# 8_-_DAC_and_MIC.net
KiCad netlist of a schematic drawn in Altium Designer
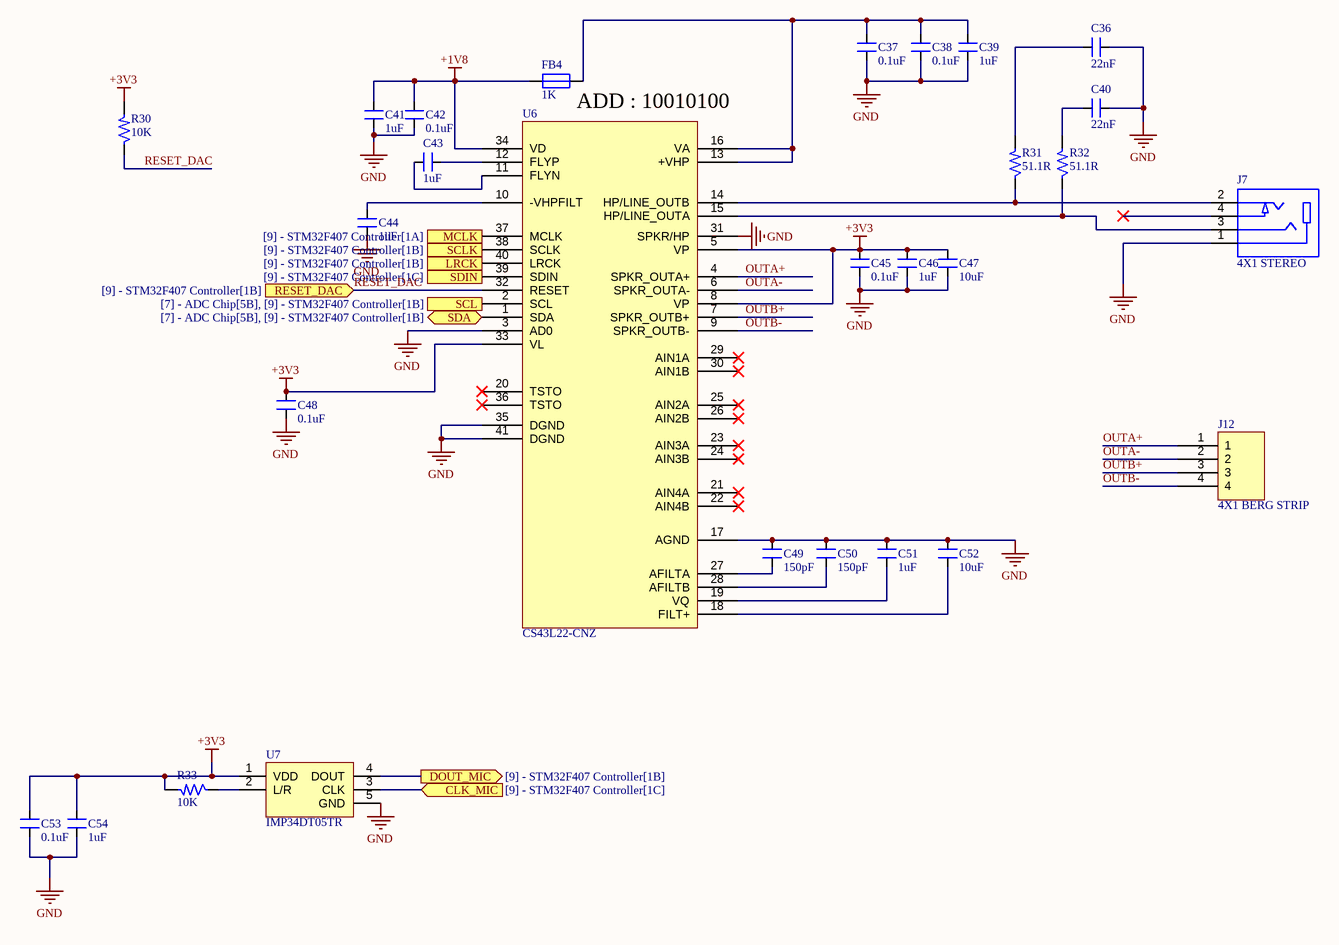
[diagram p0: [8] - DAC and MIC.SchDoc]

(export (version "E")
  (design (tool "Eeschema 10.0.6"))
  (components
    (comp (ref "C36")
      (value "22nF")
      (footprint "CAP_0805")
      (description "0.022µF ±10% 50V Ceramic Capacitor X7R 0805 (2012 Metric)")
      (fields
        (field (name "MANUFACTURER") "Samsung Electro-Mechanics")
        (field (name "MANUFACTURER PART NUMBER") "CL21B223KBANNNC")
      )
      (libsource (lib "ESTEEMPCBLIB") (part "CAP_22nF-50V-10%-0805"))
    )
    (comp (ref "C37")
      (value "0.1uF")
      (footprint "CAP_0805")
      (description "0.1µF ±10% 50V Ceramic Capacitor X7R 0805 (2012 Metric)")
      (fields
        (field (name "MANUFACTURER") "Samsung")
        (field (name "MANUFACTURER PART NUMBER") "CL21B104KBCNNNC")
      )
      (libsource (lib "ESTEEMPCBLIB") (part "CAP_0.1uF-50V-10%-0805"))
    )
    (comp (ref "C38")
      (value "0.1uF")
      (footprint "CAP_0805")
      (description "0.1µF ±10% 50V Ceramic Capacitor X7R 0805 (2012 Metric)")
      (fields
        (field (name "MANUFACTURER") "Samsung")
        (field (name "MANUFACTURER PART NUMBER") "CL21B104KBCNNNC")
      )
      (libsource (lib "ESTEEMPCBLIB") (part "CAP_0.1uF-50V-10%-0805"))
    )
    (comp (ref "C39")
      (value "1uF")
      (footprint "CAP_0805")
      (description "1µF ±5% 50V Ceramic Capacitor X7R 0805 (2012 Metric)")
      (fields
        (field (name "MANUFACTURER") "Samsung")
        (field (name "MANUFACTURER PART NUMBER") "CC0805JKX7R9BB105")
      )
      (libsource (lib "ESTEEMPCBLIB") (part "CAP_1uF-50V-5%-0805"))
    )
    (comp (ref "C40")
      (value "22nF")
      (footprint "CAP_0805")
      (description "0.022µF ±10% 50V Ceramic Capacitor X7R 0805 (2012 Metric)")
      (fields
        (field (name "MANUFACTURER") "Samsung Electro-Mechanics")
        (field (name "MANUFACTURER PART NUMBER") "CL21B223KBANNNC")
      )
      (libsource (lib "ESTEEMPCBLIB") (part "CAP_22nF-50V-10%-0805"))
    )
    (comp (ref "C41")
      (value "1uF")
      (footprint "CAP_0805")
      (description "1µF ±5% 50V Ceramic Capacitor X7R 0805 (2012 Metric)")
      (fields
        (field (name "MANUFACTURER") "Samsung")
        (field (name "MANUFACTURER PART NUMBER") "CC0805JKX7R9BB105")
      )
      (libsource (lib "ESTEEMPCBLIB") (part "CAP_1uF-50V-5%-0805"))
    )
    (comp (ref "C42")
      (value "0.1uF")
      (footprint "CAP_0805")
      (description "0.1µF ±10% 50V Ceramic Capacitor X7R 0805 (2012 Metric)")
      (fields
        (field (name "MANUFACTURER") "Samsung")
        (field (name "MANUFACTURER PART NUMBER") "CL21B104KBCNNNC")
      )
      (libsource (lib "ESTEEMPCBLIB") (part "CAP_0.1uF-50V-10%-0805"))
    )
    (comp (ref "C43")
      (value "1uF")
      (footprint "CAP_0805")
      (description "1µF ±5% 50V Ceramic Capacitor X7R 0805 (2012 Metric)")
      (fields
        (field (name "MANUFACTURER") "Samsung")
        (field (name "MANUFACTURER PART NUMBER") "CC0805JKX7R9BB105")
      )
      (libsource (lib "ESTEEMPCBLIB") (part "CAP_1uF-50V-5%-0805"))
    )
    (comp (ref "C44")
      (value "1uF")
      (footprint "CAP_0805")
      (description "1µF ±5% 50V Ceramic Capacitor X7R 0805 (2012 Metric)")
      (fields
        (field (name "MANUFACTURER") "Samsung")
        (field (name "MANUFACTURER PART NUMBER") "CC0805JKX7R9BB105")
      )
      (libsource (lib "ESTEEMPCBLIB") (part "CAP_1uF-50V-5%-0805"))
    )
    (comp (ref "C45")
      (value "0.1uF")
      (footprint "CAP_0805")
      (description "0.1µF ±10% 50V Ceramic Capacitor X7R 0805 (2012 Metric)")
      (fields
        (field (name "MANUFACTURER") "Samsung")
        (field (name "MANUFACTURER PART NUMBER") "CL21B104KBCNNNC")
      )
      (libsource (lib "ESTEEMPCBLIB") (part "CAP_0.1uF-50V-10%-0805"))
    )
    (comp (ref "C46")
      (value "1uF")
      (footprint "CAP_0805")
      (description "1µF ±5% 50V Ceramic Capacitor X7R 0805 (2012 Metric)")
      (fields
        (field (name "MANUFACTURER") "Samsung")
        (field (name "MANUFACTURER PART NUMBER") "CC0805JKX7R9BB105")
      )
      (libsource (lib "ESTEEMPCBLIB") (part "CAP_1uF-50V-5%-0805"))
    )
    (comp (ref "C47")
      (value "10uF")
      (footprint "CAP_1206")
      (description "10µF ±10% 50V Ceramic Capacitor X7R 1206 (3216 Metric)")
      (fields
        (field (name "MANUFACTURER") "KEMET")
        (field (name "MANUFACTURER PART NUMBER") "CL31B106KBHNNNE")
      )
      (libsource (lib "ESTEEMPCBLIB") (part "CAP_10uF-50V-10%-1206"))
    )
    (comp (ref "C48")
      (value "0.1uF")
      (footprint "CAP_0805")
      (description "0.1µF ±10% 50V Ceramic Capacitor X7R 0805 (2012 Metric)")
      (fields
        (field (name "MANUFACTURER") "Samsung")
        (field (name "MANUFACTURER PART NUMBER") "CL21B104KBCNNNC")
      )
      (libsource (lib "ESTEEMPCBLIB") (part "CAP_0.1uF-50V-10%-0805"))
    )
    (comp (ref "C49")
      (value "150pF")
      (footprint "CAP_0805")
      (description "150pF ±10% 50V Ceramic Capacitor C0G, NP0 0805 (2012 Metric)")
      (fields
        (field (name "MANUFACTURER") "AVX Corporation")
        (field (name "MANUFACTURER PART NUMBER") "08055A151KAT2A")
      )
      (libsource (lib "ESTEEMPCBLIB") (part "CAP_150pF-50V-10%-0805"))
    )
    (comp (ref "C50")
      (value "150pF")
      (footprint "CAP_0805")
      (description "150pF ±10% 50V Ceramic Capacitor C0G, NP0 0805 (2012 Metric)")
      (fields
        (field (name "MANUFACTURER") "AVX Corporation")
        (field (name "MANUFACTURER PART NUMBER") "08055A151KAT2A")
      )
      (libsource (lib "ESTEEMPCBLIB") (part "CAP_150pF-50V-10%-0805"))
    )
    (comp (ref "C51")
      (value "1uF")
      (footprint "CAP_0805")
      (description "1µF ±5% 50V Ceramic Capacitor X7R 0805 (2012 Metric)")
      (fields
        (field (name "MANUFACTURER") "Samsung")
        (field (name "MANUFACTURER PART NUMBER") "CC0805JKX7R9BB105")
      )
      (libsource (lib "ESTEEMPCBLIB") (part "CAP_1uF-50V-5%-0805"))
    )
    (comp (ref "C52")
      (value "10uF")
      (footprint "CAP_1206")
      (description "10µF ±10% 50V Ceramic Capacitor X7R 1206 (3216 Metric)")
      (fields
        (field (name "MANUFACTURER") "KEMET")
        (field (name "MANUFACTURER PART NUMBER") "CL31B106KBHNNNE")
      )
      (libsource (lib "ESTEEMPCBLIB") (part "CAP_10uF-50V-10%-1206"))
    )
    (comp (ref "C53")
      (value "0.1uF")
      (footprint "CAP_0805")
      (description "0.1µF ±10% 50V Ceramic Capacitor X7R 0805 (2012 Metric)")
      (fields
        (field (name "MANUFACTURER") "Samsung")
        (field (name "MANUFACTURER PART NUMBER") "CL21B104KBCNNNC")
      )
      (libsource (lib "ESTEEMPCBLIB") (part "CAP_0.1uF-50V-10%-0805"))
    )
    (comp (ref "C54")
      (value "1uF")
      (footprint "CAP_0805")
      (description "1µF ±5% 50V Ceramic Capacitor X7R 0805 (2012 Metric)")
      (fields
        (field (name "MANUFACTURER") "Samsung")
        (field (name "MANUFACTURER PART NUMBER") "CC0805JKX7R9BB105")
      )
      (libsource (lib "ESTEEMPCBLIB") (part "CAP_1uF-50V-5%-0805"))
    )
    (comp (ref "FB4")
      (value "1K")
      (footprint "IND_0805")
      (description "1 kOhms @ 100MHz 1 Power Line Ferrite Bead 0805 (2012 Metric) 1.6A")
      (fields
        (field (name "MANUFACTURER") "Laird")
        (field (name "MANUFACTURER PART NUMBER") "BLM21SP102SH1D")
      )
      (libsource (lib "ESTEEMPCBLIB") (part "FB_1K-100MHZ-1.6A-0805"))
    )
    (comp (ref "J7")
      (value "4X1 STEREO")
      (footprint "CON_SJ-2504A-SMT-TR_SMD")
      (fields
        (field (name "MANUFACTURER") "CUI Devices")
        (field (name "MANUFACTURER PART NUMBER") "SJ-2504A-SMT-TR")
      )
      (libsource (lib "ESTEEMPCBLIB") (part "CON-PLG-STEREO_4X1-100-RA-SMD"))
    )
    (comp (ref "J12")
      (value "4X1 BERG STRIP")
      (footprint "CON4_100_40D72_TH_ST_MALE")
      (description "4 Pins, 1 Row 2.54mm Pitch, Straight bergstrip, Male")
      (fields (field (name "MANUFACTURER") "NA"))
      (libsource (lib "ESTEEMPCBLIB") (part "CON-BS-PLG_4X1-100-ST-TH"))
    )
    (comp (ref "R30")
      (value "10K")
      (footprint "RES_0603")
      (description "10 kOhms ±1% 0.1W, 1/10W Chip Resistor 0603 (1608 Metric) Automotive AEC-Q200 Thick Film")
      (fields (field (name "MANUFACTURER") "Walsin") (field (name "MANUFACTURER PART NUMBER") "WR06X1002FTL"))
      (libsource (lib "ESTEEMPCBLIB") (part "RES_10K-0.1W-1%-0603"))
    )
    (comp (ref "R31")
      (value "51.1R")
      (footprint "RES_0603")
      (description "51.1 Ohms ±1% 0.1W, 1/10W Chip Resistor 0603 (1608 Metric) Thick Film")
      (fields
        (field (name "MANUFACTURER") "Vishay Dale")
        (field (name "MANUFACTURER PART NUMBER") "CRCW060351R1FKEAC")
      )
      (libsource (lib "ESTEEMPCBLIB") (part "RES_51.1R-0.1W-1%-0603"))
    )
    (comp (ref "R32")
      (value "51.1R")
      (footprint "RES_0603")
      (description "51.1 Ohms ±1% 0.1W, 1/10W Chip Resistor 0603 (1608 Metric) Thick Film")
      (fields
        (field (name "MANUFACTURER") "Vishay Dale")
        (field (name "MANUFACTURER PART NUMBER") "CRCW060351R1FKEAC")
      )
      (libsource (lib "ESTEEMPCBLIB") (part "RES_51.1R-0.1W-1%-0603"))
    )
    (comp (ref "R33")
      (value "10K")
      (footprint "RES_0603")
      (description "10 kOhms ±1% 0.1W, 1/10W Chip Resistor 0603 (1608 Metric) Automotive AEC-Q200 Thick Film")
      (fields (field (name "MANUFACTURER") "Walsin") (field (name "MANUFACTURER PART NUMBER") "WR06X1002FTL"))
      (libsource (lib "ESTEEMPCBLIB") (part "RES_10K-0.1W-1%-0603"))
    )
    (comp (ref "U6")
      (value "CS43L22-CNZ")
      (footprint "QFN40_19_284_33X9_SMD")
      (description "Audio D/A Converter ICs Low Power Stereo DAC w/ClassD Spkr Driver")
      (fields (field (name "MANUFACTURER") "Cirrus Logic"))
      (libsource (lib "ESTEEMPCBLIB") (part "IC_CS43L22"))
    )
    (comp (ref "U7")
      (value "IMP34DT05TR")
      (footprint "HCLGA-4_53_137_15X37_SMD")
      (description "MEMS Microphones AUTO & INDUSTRIAL SENSORS")
      (fields (field (name "MANUFACTURER") "STMicroelectronics"))
      (libsource (lib "ESTEEMPCBLIB") (part "IC_IMP34DT05TR"))
    )
  )
  (nets
    (net (code "1") (name "+1V8") (class "Default")
      (node (ref "C41") (pin "2") (pinfunction "2_2") (pintype "passive"))
      (node (ref "C42") (pin "2") (pinfunction "2_2") (pintype "passive"))
      (node (ref "FB4") (pin "1") (pinfunction "1_1") (pintype "passive"))
      (node (ref "U6") (pin "34") (pinfunction "VD_34") (pintype "passive"))
    )
    (net (code "2") (name "+3V3") (class "Default")
      (node (ref "C45") (pin "2") (pinfunction "2_2") (pintype "passive"))
      (node (ref "C46") (pin "2") (pinfunction "2_2") (pintype "passive"))
      (node (ref "C47") (pin "1") (pinfunction "1_1") (pintype "passive"))
      (node (ref "C48") (pin "2") (pinfunction "2_2") (pintype "passive"))
      (node (ref "C53") (pin "2") (pinfunction "2_2") (pintype "passive"))
      (node (ref "C54") (pin "2") (pinfunction "2_2") (pintype "passive"))
      (node (ref "R30") (pin "2") (pinfunction "2_2") (pintype "passive"))
      (node (ref "R33") (pin "2") (pinfunction "2_2") (pintype "passive"))
      (node (ref "U6") (pin "33") (pinfunction "VL_33") (pintype "passive"))
      (node (ref "U6") (pin "5") (pinfunction "VP_5") (pintype "passive"))
      (node (ref "U6") (pin "8") (pinfunction "VP_8") (pintype "passive"))
      (node (ref "U7") (pin "1") (pinfunction "VDD_1") (pintype "passive"))
    )
    (net (code "3") (name "/CLK_MIC") (class "Default")
      (node (ref "U7") (pin "3") (pinfunction "CLK_3") (pintype "passive"))
    )
    (net (code "4") (name "/DOUT_MIC") (class "Default")
      (node (ref "U7") (pin "4") (pinfunction "DOUT_4") (pintype "passive"))
    )
    (net (code "5") (name "/LRCK") (class "Default")
      (node (ref "U6") (pin "40") (pinfunction "LRCK_40") (pintype "passive"))
    )
    (net (code "6") (name "/MCLK") (class "Default")
      (node (ref "U6") (pin "37") (pinfunction "MCLK_37") (pintype "passive"))
    )
    (net (code "7") (name "/OUTA+") (class "Default")
      (node (ref "J12") (pin "1") (pinfunction "1_1") (pintype "passive"))
      (node (ref "U6") (pin "4") (pinfunction "SPKR_OUTA+_4") (pintype "passive"))
    )
    (net (code "8") (name "/OUTA-") (class "Default")
      (node (ref "J12") (pin "2") (pinfunction "2_2") (pintype "passive"))
      (node (ref "U6") (pin "6") (pinfunction "SPKR_OUTA-_6") (pintype "passive"))
    )
    (net (code "9") (name "/OUTB+") (class "Default")
      (node (ref "J12") (pin "3") (pinfunction "3_3") (pintype "passive"))
      (node (ref "U6") (pin "7") (pinfunction "SPKR_OUTB+_7") (pintype "passive"))
    )
    (net (code "10") (name "/OUTB-") (class "Default")
      (node (ref "J12") (pin "4") (pinfunction "4_4") (pintype "passive"))
      (node (ref "U6") (pin "9") (pinfunction "SPKR_OUTB-_9") (pintype "passive"))
    )
    (net (code "11") (name "/RESET_DAC") (class "Default")
      (node (ref "R30") (pin "1") (pinfunction "1_1") (pintype "passive"))
      (node (ref "U6") (pin "32") (pinfunction "RESET_32") (pintype "passive"))
    )
    (net (code "12") (name "/SCL") (class "Default")
      (node (ref "U6") (pin "2") (pinfunction "SCL_2") (pintype "passive"))
    )
    (net (code "13") (name "/SCLK") (class "Default")
      (node (ref "U6") (pin "38") (pinfunction "SCLK_38") (pintype "passive"))
    )
    (net (code "14") (name "/SDA") (class "Default")
      (node (ref "U6") (pin "1") (pinfunction "SDA_1") (pintype "passive"))
    )
    (net (code "15") (name "/SDIN") (class "Default")
      (node (ref "U6") (pin "39") (pinfunction "SDIN_39") (pintype "passive"))
    )
    (net (code "16") (name "GND") (class "Default")
      (node (ref "C36") (pin "2") (pinfunction "2_2") (pintype "passive"))
      (node (ref "C37") (pin "1") (pinfunction "1_1") (pintype "passive"))
      (node (ref "C38") (pin "1") (pinfunction "1_1") (pintype "passive"))
      (node (ref "C39") (pin "1") (pinfunction "1_1") (pintype "passive"))
      (node (ref "C40") (pin "2") (pinfunction "2_2") (pintype "passive"))
      (node (ref "C41") (pin "1") (pinfunction "1_1") (pintype "passive"))
      (node (ref "C42") (pin "1") (pinfunction "1_1") (pintype "passive"))
      (node (ref "C44") (pin "2") (pinfunction "2_2") (pintype "passive"))
      (node (ref "C45") (pin "1") (pinfunction "1_1") (pintype "passive"))
      (node (ref "C46") (pin "1") (pinfunction "1_1") (pintype "passive"))
      (node (ref "C47") (pin "2") (pinfunction "2_2") (pintype "passive"))
      (node (ref "C48") (pin "1") (pinfunction "1_1") (pintype "passive"))
      (node (ref "C49") (pin "2") (pinfunction "2_2") (pintype "passive"))
      (node (ref "C50") (pin "2") (pinfunction "2_2") (pintype "passive"))
      (node (ref "C51") (pin "2") (pinfunction "2_2") (pintype "passive"))
      (node (ref "C52") (pin "2") (pinfunction "2_2") (pintype "passive"))
      (node (ref "C53") (pin "1") (pinfunction "1_1") (pintype "passive"))
      (node (ref "C54") (pin "1") (pinfunction "1_1") (pintype "passive"))
      (node (ref "J7") (pin "1") (pinfunction "1_1") (pintype "passive"))
      (node (ref "U6") (pin "17") (pinfunction "AGND_17") (pintype "passive"))
      (node (ref "U6") (pin "3") (pinfunction "AD0_3") (pintype "passive"))
      (node (ref "U6") (pin "31") (pinfunction "SPKR/HP_31") (pintype "passive"))
      (node (ref "U6") (pin "35") (pinfunction "DGND_35") (pintype "passive"))
      (node (ref "U6") (pin "41") (pinfunction "DGND_41") (pintype "passive"))
      (node (ref "U7") (pin "5") (pinfunction "GND_5") (pintype "passive"))
    )
    (net (code "17") (name "Net-(C36-Pad1)") (class "Default")
      (node (ref "C36") (pin "1") (pinfunction "1_1") (pintype "passive"))
      (node (ref "R31") (pin "2") (pinfunction "2_2") (pintype "passive"))
    )
    (net (code "18") (name "Net-(C40-Pad1)") (class "Default")
      (node (ref "C40") (pin "1") (pinfunction "1_1") (pintype "passive"))
      (node (ref "R32") (pin "2") (pinfunction "2_2") (pintype "passive"))
    )
    (net (code "19") (name "Net-(U6-+VHP)") (class "Default")
      (node (ref "C37") (pin "2") (pinfunction "2_2") (pintype "passive"))
      (node (ref "C38") (pin "2") (pinfunction "2_2") (pintype "passive"))
      (node (ref "C39") (pin "2") (pinfunction "2_2") (pintype "passive"))
      (node (ref "FB4") (pin "2") (pinfunction "2_2") (pintype "passive"))
      (node (ref "U6") (pin "13") (pinfunction "+VHP_13") (pintype "passive"))
      (node (ref "U6") (pin "16") (pinfunction "VA_16") (pintype "passive"))
    )
    (net (code "20") (name "Net-(U6--VHPFILT)") (class "Default")
      (node (ref "C44") (pin "1") (pinfunction "1_1") (pintype "passive"))
      (node (ref "U6") (pin "10") (pinfunction "-VHPFILT_10") (pintype "passive"))
    )
    (net (code "21") (name "Net-(U6-AFILTA)") (class "Default")
      (node (ref "C49") (pin "1") (pinfunction "1_1") (pintype "passive"))
      (node (ref "U6") (pin "27") (pinfunction "AFILTA_27") (pintype "passive"))
    )
    (net (code "22") (name "Net-(U6-AFILTB)") (class "Default")
      (node (ref "C50") (pin "1") (pinfunction "1_1") (pintype "passive"))
      (node (ref "U6") (pin "28") (pinfunction "AFILTB_28") (pintype "passive"))
    )
    (net (code "23") (name "Net-(U6-FILT+)") (class "Default")
      (node (ref "C52") (pin "1") (pinfunction "1_1") (pintype "passive"))
      (node (ref "U6") (pin "18") (pinfunction "FILT+_18") (pintype "passive"))
    )
    (net (code "24") (name "Net-(U6-FLYN)") (class "Default")
      (node (ref "C43") (pin "2") (pinfunction "2_2") (pintype "passive"))
      (node (ref "U6") (pin "11") (pinfunction "FLYN_11") (pintype "passive"))
    )
    (net (code "25") (name "Net-(U6-FLYP)") (class "Default")
      (node (ref "C43") (pin "1") (pinfunction "1_1") (pintype "passive"))
      (node (ref "U6") (pin "12") (pinfunction "FLYP_12") (pintype "passive"))
    )
    (net (code "26") (name "Net-(U6-HP{slash}LINE_OUTA)") (class "Default")
      (node (ref "J7") (pin "3") (pinfunction "3_3") (pintype "passive"))
      (node (ref "R32") (pin "1") (pinfunction "1_1") (pintype "passive"))
      (node (ref "U6") (pin "15") (pinfunction "HP/LINE_OUTA_15") (pintype "passive"))
    )
    (net (code "27") (name "Net-(U6-HP{slash}LINE_OUTB)") (class "Default")
      (node (ref "J7") (pin "2") (pinfunction "2_2") (pintype "passive"))
      (node (ref "R31") (pin "1") (pinfunction "1_1") (pintype "passive"))
      (node (ref "U6") (pin "14") (pinfunction "HP/LINE_OUTB_14") (pintype "passive"))
    )
    (net (code "28") (name "Net-(U6-VQ)") (class "Default")
      (node (ref "C51") (pin "1") (pinfunction "1_1") (pintype "passive"))
      (node (ref "U6") (pin "19") (pinfunction "VQ_19") (pintype "passive"))
    )
    (net (code "29") (name "Net-(U7-L{slash}R)") (class "Default")
      (node (ref "R33") (pin "1") (pinfunction "1_1") (pintype "passive"))
      (node (ref "U7") (pin "2") (pinfunction "L/R_2") (pintype "passive"))
    )
    (net (code "30") (name "unconnected-(J7-Pad4)") (class "Default")
      (node (ref "J7") (pin "4") (pinfunction "4_4") (pintype "passive+no_connect"))
    )
    (net (code "31") (name "unconnected-(U6-AIN1A-Pad29)") (class "Default")
      (node (ref "U6") (pin "29") (pinfunction "AIN1A_29") (pintype "passive+no_connect"))
    )
    (net (code "32") (name "unconnected-(U6-AIN1B-Pad30)") (class "Default")
      (node (ref "U6") (pin "30") (pinfunction "AIN1B_30") (pintype "passive+no_connect"))
    )
    (net (code "33") (name "unconnected-(U6-AIN2A-Pad25)") (class "Default")
      (node (ref "U6") (pin "25") (pinfunction "AIN2A_25") (pintype "passive+no_connect"))
    )
    (net (code "34") (name "unconnected-(U6-AIN2B-Pad26)") (class "Default")
      (node (ref "U6") (pin "26") (pinfunction "AIN2B_26") (pintype "passive+no_connect"))
    )
    (net (code "35") (name "unconnected-(U6-AIN3A-Pad23)") (class "Default")
      (node (ref "U6") (pin "23") (pinfunction "AIN3A_23") (pintype "passive+no_connect"))
    )
    (net (code "36") (name "unconnected-(U6-AIN3B-Pad24)") (class "Default")
      (node (ref "U6") (pin "24") (pinfunction "AIN3B_24") (pintype "passive+no_connect"))
    )
    (net (code "37") (name "unconnected-(U6-AIN4A-Pad21)") (class "Default")
      (node (ref "U6") (pin "21") (pinfunction "AIN4A_21") (pintype "passive+no_connect"))
    )
    (net (code "38") (name "unconnected-(U6-AIN4B-Pad22)") (class "Default")
      (node (ref "U6") (pin "22") (pinfunction "AIN4B_22") (pintype "passive+no_connect"))
    )
    (net (code "39") (name "unconnected-(U6-TSTO-Pad20)") (class "Default")
      (node (ref "U6") (pin "20") (pinfunction "TSTO_20") (pintype "passive+no_connect"))
    )
    (net (code "40") (name "unconnected-(U6-TSTO-Pad36)") (class "Default")
      (node (ref "U6") (pin "36") (pinfunction "TSTO_36") (pintype "passive+no_connect"))
    )
  )
)
